# flowhw.net
KiCad netlist of a schematic drawn in Altium Designer
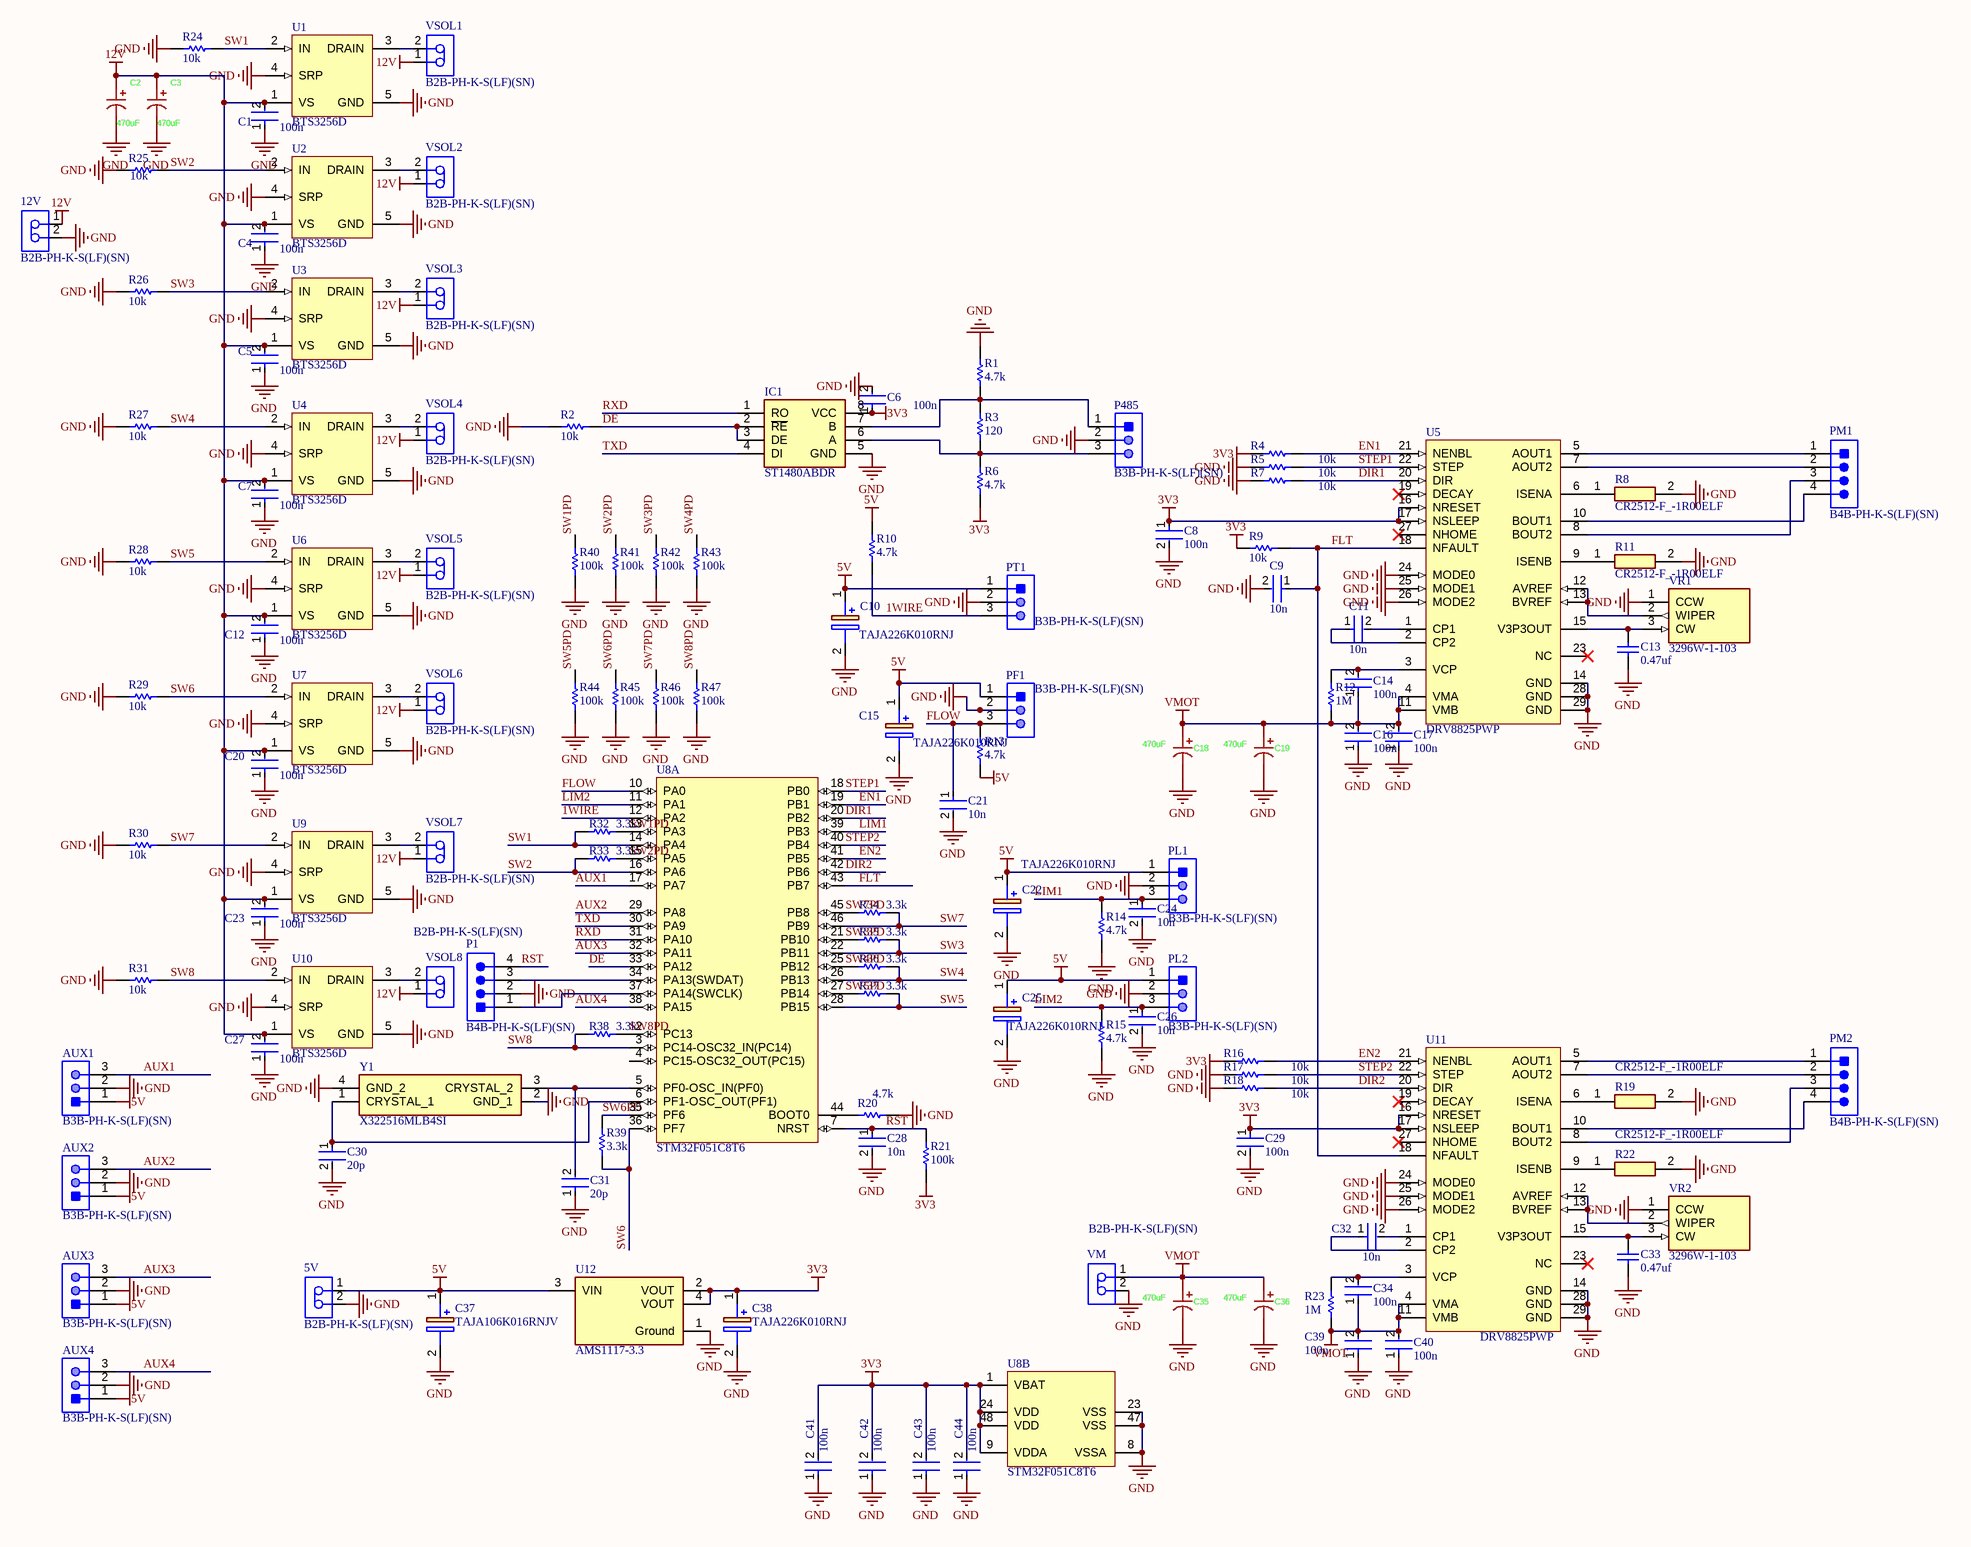
[diagram p0: flowhw.SchDoc]

(export (version "E")
  (design (tool "Eeschema 10.0.6"))
  (components
    (comp (ref "5V")
      (value "B2B-PH-K-S(LF)(SN)")
      (footprint "JST-B2B-PH-K-S_V")
      (fields (field (name "MANUFACTURER") "JST"))
      (libsource (lib "Altium Content Vault") (part "CN-2P-F-QF2"))
    )
    (comp (ref "12V")
      (value "B2B-PH-K-S(LF)(SN)")
      (footprint "JST-B2B-PH-K-S_V")
      (fields (field (name "MANUFACTURER") "JST"))
      (libsource (lib "Altium Content Vault") (part "CN-2P-F-QF2"))
    )
    (comp (ref "AUX1")
      (value "B3B-PH-K-S(LF)(SN)")
      (footprint "JST-B3B-PH-K-S-3_V")
      (fields (field (name "MANUFACTURER") "JST"))
      (libsource (lib "Altium Content Vault") (part "CN-1P-M-R3"))
    )
    (comp (ref "AUX2")
      (value "B3B-PH-K-S(LF)(SN)")
      (footprint "JST-B3B-PH-K-S-3_V")
      (fields (field (name "MANUFACTURER") "JST"))
      (libsource (lib "Altium Content Vault") (part "CN-1P-M-R3"))
    )
    (comp (ref "AUX3")
      (value "B3B-PH-K-S(LF)(SN)")
      (footprint "JST-B3B-PH-K-S-3_V")
      (fields (field (name "MANUFACTURER") "JST"))
      (libsource (lib "Altium Content Vault") (part "CN-1P-M-R3"))
    )
    (comp (ref "AUX4")
      (value "B3B-PH-K-S(LF)(SN)")
      (footprint "JST-B3B-PH-K-S-3_V")
      (fields (field (name "MANUFACTURER") "JST"))
      (libsource (lib "Altium Content Vault") (part "CN-1P-M-R3"))
    )
    (comp (ref "C1")
      (value "100n")
      (footprint "FP-C0402-BB-MFG")
      (description "C0402 8.2 pF C0G 0.5 pF 50 V")
      (fields
        (field (name "OCTOPART") "https://octopart.com/c0402c829d5gacauto-kemet-89441553")
        (field (name "TOLERANCE") "0.5 pF")
      )
      (libsource (lib "Altium Content Vault") (part "b4654b650e69147ec39a6b967a45e02"))
    )
    (comp (ref "C2")
      (value "470uF")
      (footprint "470UF")
      (fields
        (field (name "MANUFACTURER") "AISHI(艾华集团)")
        (field (name "MANUFACTURER PART") "SPZ1VM471G13O00RAXXX")
        (field (name "TOLERANCE") "±20%")
      )
      (libsource (lib "altium-import") (part "root_3_SPZ1VM471G13O00RAXXX_"))
    )
    (comp (ref "C3")
      (value "470uF")
      (footprint "470UF")
      (fields
        (field (name "MANUFACTURER") "AISHI(艾华集团)")
        (field (name "MANUFACTURER PART") "SPZ1VM471G13O00RAXXX")
        (field (name "TOLERANCE") "±20%")
      )
      (libsource (lib "altium-import") (part "root_3_SPZ1VM471G13O00RAXXX_"))
    )
    (comp (ref "C4")
      (value "100n")
      (footprint "FP-C0402-BB-MFG")
      (description "C0402 8.2 pF C0G 0.5 pF 50 V")
      (fields
        (field (name "OCTOPART") "https://octopart.com/c0402c829d5gacauto-kemet-89441553")
        (field (name "TOLERANCE") "0.5 pF")
      )
      (libsource (lib "Altium Content Vault") (part "b4654b650e69147ec39a6b967a45e02"))
    )
    (comp (ref "C5")
      (value "100n")
      (footprint "FP-C0402-BB-MFG")
      (description "C0402 8.2 pF C0G 0.5 pF 50 V")
      (fields
        (field (name "OCTOPART") "https://octopart.com/c0402c829d5gacauto-kemet-89441553")
        (field (name "TOLERANCE") "0.5 pF")
      )
      (libsource (lib "Altium Content Vault") (part "b4654b650e69147ec39a6b967a45e02"))
    )
    (comp (ref "C6")
      (value "100n")
      (footprint "FP-C0402-BB-MFG")
      (description "C0402 8.2 pF C0G 0.5 pF 50 V")
      (fields
        (field (name "OCTOPART") "https://octopart.com/c0402c829d5gacauto-kemet-89441553")
        (field (name "TOLERANCE") "0.5 pF")
      )
      (libsource (lib "Altium Content Vault") (part "b4654b650e69147ec39a6b967a45e02"))
    )
    (comp (ref "C7")
      (value "100n")
      (footprint "FP-C0402-BB-MFG")
      (description "C0402 8.2 pF C0G 0.5 pF 50 V")
      (fields
        (field (name "OCTOPART") "https://octopart.com/c0402c829d5gacauto-kemet-89441553")
        (field (name "TOLERANCE") "0.5 pF")
      )
      (libsource (lib "Altium Content Vault") (part "b4654b650e69147ec39a6b967a45e02"))
    )
    (comp (ref "C8")
      (value "100n")
      (footprint "FP-C0402-BB-MFG")
      (description "C0402 8.2 pF C0G 0.5 pF 50 V")
      (fields
        (field (name "OCTOPART") "https://octopart.com/c0402c829d5gacauto-kemet-89441553")
        (field (name "TOLERANCE") "0.5 pF")
      )
      (libsource (lib "Altium Content Vault") (part "b4654b650e69147ec39a6b967a45e02"))
    )
    (comp (ref "C9")
      (value "10n")
      (footprint "FP-C0402-BB-MFG")
      (description "C0402 8.2 pF C0G 0.5 pF 50 V")
      (fields
        (field (name "OCTOPART") "https://octopart.com/c0402c829d5gacauto-kemet-89441553")
        (field (name "TOLERANCE") "0.5 pF")
      )
      (libsource (lib "Altium Content Vault") (part "b4654b650e69147ec39a6b967a45e02"))
    )
    (comp (ref "C10")
      (value "TAJA226K010RNJ")
      (footprint "SamacSys:CAPPM3216X180N")
      (description "Capacitor Polarised")
      (fields (field (name "MOUSER PART NUMBER") "581-TAJA226K010R"))
      (libsource (lib "*") (part "TAJA226K010RNJ"))
    )
    (comp (ref "C11")
      (value "10n")
      (footprint "FP-C0402-BB-MFG")
      (description "C0402 8.2 pF C0G 0.5 pF 50 V")
      (fields
        (field (name "OCTOPART") "https://octopart.com/c0402c829d5gacauto-kemet-89441553")
        (field (name "TOLERANCE") "0.5 pF")
      )
      (libsource (lib "Altium Content Vault") (part "b4654b650e69147ec39a6b967a45e02"))
    )
    (comp (ref "C12")
      (value "100n")
      (footprint "FP-C0402-BB-MFG")
      (description "C0402 8.2 pF C0G 0.5 pF 50 V")
      (fields
        (field (name "OCTOPART") "https://octopart.com/c0402c829d5gacauto-kemet-89441553")
        (field (name "TOLERANCE") "0.5 pF")
      )
      (libsource (lib "Altium Content Vault") (part "b4654b650e69147ec39a6b967a45e02"))
    )
    (comp (ref "C13")
      (value "0.47uf")
      (footprint "CAPC1608X90X35LL15T15")
      (fields
        (field (name "MANUFACTURER") "AVX Interconnect / Elco")
        (field (name "PART NUMBER") "0603ZC101KAT2A")
      )
      (libsource (lib "Altium Content Vault") (part "CAP"))
    )
    (comp (ref "C14")
      (value "100n")
      (footprint "FP-C0402-BB-MFG")
      (description "C0402 8.2 pF C0G 0.5 pF 50 V")
      (fields
        (field (name "OCTOPART") "https://octopart.com/c0402c829d5gacauto-kemet-89441553")
        (field (name "TOLERANCE") "0.5 pF")
      )
      (libsource (lib "Altium Content Vault") (part "b4654b650e69147ec39a6b967a45e02"))
    )
    (comp (ref "C15")
      (value "TAJA226K010RNJ")
      (footprint "SamacSys:CAPPM3216X180N")
      (description "Capacitor Polarised")
      (fields (field (name "MOUSER PART NUMBER") "581-TAJA226K010R"))
      (libsource (lib "*") (part "TAJA226K010RNJ"))
    )
    (comp (ref "C16")
      (value "100n")
      (footprint "FP-C0402-BB-MFG")
      (description "C0402 8.2 pF C0G 0.5 pF 50 V")
      (fields
        (field (name "OCTOPART") "https://octopart.com/c0402c829d5gacauto-kemet-89441553")
        (field (name "TOLERANCE") "0.5 pF")
      )
      (libsource (lib "Altium Content Vault") (part "b4654b650e69147ec39a6b967a45e02"))
    )
    (comp (ref "C17")
      (value "100n")
      (footprint "FP-C0402-BB-MFG")
      (description "C0402 8.2 pF C0G 0.5 pF 50 V")
      (fields
        (field (name "OCTOPART") "https://octopart.com/c0402c829d5gacauto-kemet-89441553")
        (field (name "TOLERANCE") "0.5 pF")
      )
      (libsource (lib "Altium Content Vault") (part "b4654b650e69147ec39a6b967a45e02"))
    )
    (comp (ref "C18")
      (value "470uF")
      (footprint "470UF")
      (fields
        (field (name "MANUFACTURER") "AISHI(艾华集团)")
        (field (name "MANUFACTURER PART") "SPZ1VM471G13O00RAXXX")
        (field (name "TOLERANCE") "±20%")
      )
      (libsource (lib "altium-import") (part "root_3_SPZ1VM471G13O00RAXXX_"))
    )
    (comp (ref "C19")
      (value "470uF")
      (footprint "470UF")
      (fields
        (field (name "MANUFACTURER") "AISHI(艾华集团)")
        (field (name "MANUFACTURER PART") "SPZ1VM471G13O00RAXXX")
        (field (name "TOLERANCE") "±20%")
      )
      (libsource (lib "altium-import") (part "root_3_SPZ1VM471G13O00RAXXX_"))
    )
    (comp (ref "C20")
      (value "100n")
      (footprint "FP-C0402-BB-MFG")
      (description "C0402 8.2 pF C0G 0.5 pF 50 V")
      (fields
        (field (name "OCTOPART") "https://octopart.com/c0402c829d5gacauto-kemet-89441553")
        (field (name "TOLERANCE") "0.5 pF")
      )
      (libsource (lib "Altium Content Vault") (part "b4654b650e69147ec39a6b967a45e02"))
    )
    (comp (ref "C21")
      (value "10n")
      (footprint "FP-C0402-BB-MFG")
      (description "C0402 8.2 pF C0G 0.5 pF 50 V")
      (fields
        (field (name "OCTOPART") "https://octopart.com/c0402c829d5gacauto-kemet-89441553")
        (field (name "TOLERANCE") "0.5 pF")
      )
      (libsource (lib "Altium Content Vault") (part "b4654b650e69147ec39a6b967a45e02"))
    )
    (comp (ref "C22")
      (value "TAJA226K010RNJ")
      (footprint "SamacSys:CAPPM3216X180N")
      (description "Capacitor Polarised")
      (fields (field (name "MOUSER PART NUMBER") "581-TAJA226K010R"))
      (libsource (lib "*") (part "TAJA226K010RNJ"))
    )
    (comp (ref "C23")
      (value "100n")
      (footprint "FP-C0402-BB-MFG")
      (description "C0402 8.2 pF C0G 0.5 pF 50 V")
      (fields
        (field (name "OCTOPART") "https://octopart.com/c0402c829d5gacauto-kemet-89441553")
        (field (name "TOLERANCE") "0.5 pF")
      )
      (libsource (lib "Altium Content Vault") (part "b4654b650e69147ec39a6b967a45e02"))
    )
    (comp (ref "C24")
      (value "10n")
      (footprint "FP-C0402-BB-MFG")
      (description "C0402 8.2 pF C0G 0.5 pF 50 V")
      (fields
        (field (name "OCTOPART") "https://octopart.com/c0402c829d5gacauto-kemet-89441553")
        (field (name "TOLERANCE") "0.5 pF")
      )
      (libsource (lib "Altium Content Vault") (part "b4654b650e69147ec39a6b967a45e02"))
    )
    (comp (ref "C25")
      (value "TAJA226K010RNJ")
      (footprint "SamacSys:CAPPM3216X180N")
      (description "Capacitor Polarised")
      (fields (field (name "MOUSER PART NUMBER") "581-TAJA226K010R"))
      (libsource (lib "*") (part "TAJA226K010RNJ"))
    )
    (comp (ref "C26")
      (value "10n")
      (footprint "FP-C0402-BB-MFG")
      (description "C0402 8.2 pF C0G 0.5 pF 50 V")
      (fields
        (field (name "OCTOPART") "https://octopart.com/c0402c829d5gacauto-kemet-89441553")
        (field (name "TOLERANCE") "0.5 pF")
      )
      (libsource (lib "Altium Content Vault") (part "b4654b650e69147ec39a6b967a45e02"))
    )
    (comp (ref "C27")
      (value "100n")
      (footprint "FP-C0402-BB-MFG")
      (description "C0402 8.2 pF C0G 0.5 pF 50 V")
      (fields
        (field (name "OCTOPART") "https://octopart.com/c0402c829d5gacauto-kemet-89441553")
        (field (name "TOLERANCE") "0.5 pF")
      )
      (libsource (lib "Altium Content Vault") (part "b4654b650e69147ec39a6b967a45e02"))
    )
    (comp (ref "C28")
      (value "10n")
      (footprint "FP-C0402-BB-MFG")
      (description "C0402 8.2 pF C0G 0.5 pF 50 V")
      (fields
        (field (name "OCTOPART") "https://octopart.com/c0402c829d5gacauto-kemet-89441553")
        (field (name "TOLERANCE") "0.5 pF")
      )
      (libsource (lib "Altium Content Vault") (part "b4654b650e69147ec39a6b967a45e02"))
    )
    (comp (ref "C29")
      (value "100n")
      (footprint "FP-C0402-BB-MFG")
      (description "C0402 8.2 pF C0G 0.5 pF 50 V")
      (fields
        (field (name "OCTOPART") "https://octopart.com/c0402c829d5gacauto-kemet-89441553")
        (field (name "TOLERANCE") "0.5 pF")
      )
      (libsource (lib "Altium Content Vault") (part "b4654b650e69147ec39a6b967a45e02"))
    )
    (comp (ref "C30")
      (value "20p")
      (footprint "FP-C0402-BB-MFG")
      (description "C0402 8.2 pF C0G 0.5 pF 50 V")
      (fields
        (field (name "OCTOPART") "https://octopart.com/c0402c829d5gacauto-kemet-89441553")
        (field (name "TOLERANCE") "0.5 pF")
      )
      (libsource (lib "Altium Content Vault") (part "b4654b650e69147ec39a6b967a45e02"))
    )
    (comp (ref "C31")
      (value "20p")
      (footprint "FP-C0402-BB-MFG")
      (description "C0402 8.2 pF C0G 0.5 pF 50 V")
      (fields
        (field (name "OCTOPART") "https://octopart.com/c0402c829d5gacauto-kemet-89441553")
        (field (name "TOLERANCE") "0.5 pF")
      )
      (libsource (lib "Altium Content Vault") (part "b4654b650e69147ec39a6b967a45e02"))
    )
    (comp (ref "C32")
      (value "10n")
      (footprint "FP-C0402-BB-MFG")
      (description "C0402 8.2 pF C0G 0.5 pF 50 V")
      (fields
        (field (name "OCTOPART") "https://octopart.com/c0402c829d5gacauto-kemet-89441553")
        (field (name "TOLERANCE") "0.5 pF")
      )
      (libsource (lib "Altium Content Vault") (part "b4654b650e69147ec39a6b967a45e02"))
    )
    (comp (ref "C33")
      (value "0.47uf")
      (footprint "CAPC1608X90X35LL15T15")
      (fields
        (field (name "MANUFACTURER") "AVX Interconnect / Elco")
        (field (name "PART NUMBER") "0603ZC101KAT2A")
      )
      (libsource (lib "Altium Content Vault") (part "CAP"))
    )
    (comp (ref "C34")
      (value "100n")
      (footprint "FP-C0402-BB-MFG")
      (description "C0402 8.2 pF C0G 0.5 pF 50 V")
      (fields
        (field (name "OCTOPART") "https://octopart.com/c0402c829d5gacauto-kemet-89441553")
        (field (name "TOLERANCE") "0.5 pF")
      )
      (libsource (lib "Altium Content Vault") (part "b4654b650e69147ec39a6b967a45e02"))
    )
    (comp (ref "C35")
      (value "470uF")
      (footprint "470UF")
      (fields
        (field (name "MANUFACTURER") "AISHI(艾华集团)")
        (field (name "MANUFACTURER PART") "SPZ1VM471G13O00RAXXX")
        (field (name "TOLERANCE") "±20%")
      )
      (libsource (lib "altium-import") (part "root_3_SPZ1VM471G13O00RAXXX_"))
    )
    (comp (ref "C36")
      (value "470uF")
      (footprint "470UF")
      (fields
        (field (name "MANUFACTURER") "AISHI(艾华集团)")
        (field (name "MANUFACTURER PART") "SPZ1VM471G13O00RAXXX")
        (field (name "TOLERANCE") "±20%")
      )
      (libsource (lib "altium-import") (part "root_3_SPZ1VM471G13O00RAXXX_"))
    )
    (comp (ref "C37")
      (value "TAJA106K016RNJV")
      (footprint "SamacSys:CAPPM3216X180N")
      (description "Capacitor Polarised")
      (fields (field (name "MOUSER PART NUMBER") "581-TAJA106K016RNJV"))
      (libsource (lib "*") (part "TAJA106K016RNJV"))
    )
    (comp (ref "C38")
      (value "TAJA226K010RNJ")
      (footprint "SamacSys:CAPPM3216X180N")
      (description "Capacitor Polarised")
      (fields (field (name "MOUSER PART NUMBER") "581-TAJA226K010R"))
      (libsource (lib "*") (part "TAJA226K010RNJ"))
    )
    (comp (ref "C39")
      (value "100n")
      (footprint "FP-C0402-BB-MFG")
      (description "C0402 8.2 pF C0G 0.5 pF 50 V")
      (fields
        (field (name "OCTOPART") "https://octopart.com/c0402c829d5gacauto-kemet-89441553")
        (field (name "TOLERANCE") "0.5 pF")
      )
      (libsource (lib "Altium Content Vault") (part "b4654b650e69147ec39a6b967a45e02"))
    )
    (comp (ref "C40")
      (value "100n")
      (footprint "FP-C0402-BB-MFG")
      (description "C0402 8.2 pF C0G 0.5 pF 50 V")
      (fields
        (field (name "OCTOPART") "https://octopart.com/c0402c829d5gacauto-kemet-89441553")
        (field (name "TOLERANCE") "0.5 pF")
      )
      (libsource (lib "Altium Content Vault") (part "b4654b650e69147ec39a6b967a45e02"))
    )
    (comp (ref "C41")
      (value "100n")
      (footprint "FP-C0402-BB-MFG")
      (description "C0402 8.2 pF C0G 0.5 pF 50 V")
      (fields
        (field (name "OCTOPART") "https://octopart.com/c0402c829d5gacauto-kemet-89441553")
        (field (name "TOLERANCE") "0.5 pF")
      )
      (libsource (lib "Altium Content Vault") (part "b4654b650e69147ec39a6b967a45e02"))
    )
    (comp (ref "C42")
      (value "100n")
      (footprint "FP-C0402-BB-MFG")
      (description "C0402 8.2 pF C0G 0.5 pF 50 V")
      (fields
        (field (name "OCTOPART") "https://octopart.com/c0402c829d5gacauto-kemet-89441553")
        (field (name "TOLERANCE") "0.5 pF")
      )
      (libsource (lib "Altium Content Vault") (part "b4654b650e69147ec39a6b967a45e02"))
    )
    (comp (ref "C43")
      (value "100n")
      (footprint "FP-C0402-BB-MFG")
      (description "C0402 8.2 pF C0G 0.5 pF 50 V")
      (fields
        (field (name "OCTOPART") "https://octopart.com/c0402c829d5gacauto-kemet-89441553")
        (field (name "TOLERANCE") "0.5 pF")
      )
      (libsource (lib "Altium Content Vault") (part "b4654b650e69147ec39a6b967a45e02"))
    )
    (comp (ref "C44")
      (value "100n")
      (footprint "FP-C0402-BB-MFG")
      (description "C0402 8.2 pF C0G 0.5 pF 50 V")
      (fields
        (field (name "OCTOPART") "https://octopart.com/c0402c829d5gacauto-kemet-89441553")
        (field (name "TOLERANCE") "0.5 pF")
      )
      (libsource (lib "Altium Content Vault") (part "b4654b650e69147ec39a6b967a45e02"))
    )
    (comp (ref "IC1")
      (value "ST1480ABDR")
      (footprint "SamacSys:SOIC127P600X175-8N")
      (description "Integrated Circuit")
      (fields (field (name "MOUSER PART NUMBER") "511-ST1480ABDR"))
      (libsource (lib "*") (part "ST1480ABDR"))
    )
    (comp (ref "P1")
      (value "B4B-PH-K-S(LF)(SN)")
      (footprint "JST-B4B-PH-K-S_V")
      (fields (field (name "MANUFACTURER") "JST"))
      (libsource (lib "") (part "CN-1P-M-R4_1"))
    )
    (comp (ref "P485")
      (value "B3B-PH-K-S(LF)(SN)")
      (footprint "JST-B3B-PH-K-S-3_V")
      (fields (field (name "MANUFACTURER") "JST"))
      (libsource (lib "") (part "CN-1P-M-R3_1"))
    )
    (comp (ref "PF1")
      (value "B3B-PH-K-S(LF)(SN)")
      (footprint "JST-B3B-PH-K-S-3_V")
      (fields (field (name "MANUFACTURER") "JST"))
      (libsource (lib "") (part "CN-1P-M-R3_1"))
    )
    (comp (ref "PL1")
      (value "B3B-PH-K-S(LF)(SN)")
      (footprint "JST-B3B-PH-K-S-3_V")
      (fields (field (name "MANUFACTURER") "JST"))
      (libsource (lib "") (part "CN-1P-M-R3_1"))
    )
    (comp (ref "PL2")
      (value "B3B-PH-K-S(LF)(SN)")
      (footprint "JST-B3B-PH-K-S-3_V")
      (fields (field (name "MANUFACTURER") "JST"))
      (libsource (lib "") (part "CN-1P-M-R3_1"))
    )
    (comp (ref "PM1")
      (value "B4B-PH-K-S(LF)(SN)")
      (footprint "JST-B4B-PH-K-S_V")
      (fields (field (name "MANUFACTURER") "JST"))
      (libsource (lib "Altium Content Vault") (part "CN-1P-M-R4"))
    )
    (comp (ref "PM2")
      (value "B4B-PH-K-S(LF)(SN)")
      (footprint "JST-B4B-PH-K-S_V")
      (fields (field (name "MANUFACTURER") "JST"))
      (libsource (lib "Altium Content Vault") (part "CN-1P-M-R4"))
    )
    (comp (ref "PT1")
      (value "B3B-PH-K-S(LF)(SN)")
      (footprint "JST-B3B-PH-K-S-3_V")
      (fields (field (name "MANUFACTURER") "JST"))
      (libsource (lib "") (part "CN-1P-M-R3_1"))
    )
    (comp (ref "R1")
      (value "4.7k")
      (footprint "RESC1005X40X25LL05T10")
      (fields (field (name "PART NUMBER") "RC0402FR-0720R5L") (field (name "MANUFACTURER") "Yageo / Phycomp"))
      (libsource (lib "Altium Content Vault") (part "RES"))
    )
    (comp (ref "R2")
      (value "10k")
      (footprint "RESC1005X40X25LL05T10")
      (fields (field (name "PART NUMBER") "RC0402FR-0720R5L") (field (name "MANUFACTURER") "Yageo / Phycomp"))
      (libsource (lib "Altium Content Vault") (part "RES"))
    )
    (comp (ref "R3")
      (value "120")
      (footprint "RESC1005X40X25LL05T10")
      (fields (field (name "PART NUMBER") "RC0402FR-0720R5L") (field (name "MANUFACTURER") "Yageo / Phycomp"))
      (libsource (lib "Altium Content Vault") (part "RES"))
    )
    (comp (ref "R4")
      (value "10k")
      (footprint "RESC1005X40X25LL05T10")
      (fields (field (name "PART NUMBER") "RC0402FR-0720R5L") (field (name "MANUFACTURER") "Yageo / Phycomp"))
      (libsource (lib "Altium Content Vault") (part "RES"))
    )
    (comp (ref "R5")
      (value "10k")
      (footprint "RESC1005X40X25LL05T10")
      (fields (field (name "PART NUMBER") "RC0402FR-0720R5L") (field (name "MANUFACTURER") "Yageo / Phycomp"))
      (libsource (lib "Altium Content Vault") (part "RES"))
    )
    (comp (ref "R6")
      (value "4.7k")
      (footprint "RESC1005X40X25LL05T10")
      (fields (field (name "PART NUMBER") "RC0402FR-0720R5L") (field (name "MANUFACTURER") "Yageo / Phycomp"))
      (libsource (lib "Altium Content Vault") (part "RES"))
    )
    (comp (ref "R7")
      (value "10k")
      (footprint "RESC1005X40X25LL05T10")
      (fields (field (name "PART NUMBER") "RC0402FR-0720R5L") (field (name "MANUFACTURER") "Yageo / Phycomp"))
      (libsource (lib "Altium Content Vault") (part "RES"))
    )
    (comp (ref "R8")
      (value "CR2512-F_-1R00ELF")
      (footprint "SamacSys:RESC6331X75N")
      (description "Resistor")
      (fields
        (field (name "MANUFACTURER_PART_NUMBER") "CR2512-F/-1R00ELF")
        (field (name "MOUSER PART NUMBER") "652-CR2512-F/1R00ELF")
      )
      (libsource (lib "*") (part "CR2512-F_-1R00ELF"))
    )
    (comp (ref "R9")
      (value "10k")
      (footprint "RESC1005X40X25LL05T10")
      (fields (field (name "PART NUMBER") "RC0402FR-0720R5L") (field (name "MANUFACTURER") "Yageo / Phycomp"))
      (libsource (lib "Altium Content Vault") (part "RES"))
    )
    (comp (ref "R10")
      (value "4.7k")
      (footprint "RESC1005X40X25LL05T10")
      (fields (field (name "PART NUMBER") "RC0402FR-0720R5L") (field (name "MANUFACTURER") "Yageo / Phycomp"))
      (libsource (lib "Altium Content Vault") (part "RES"))
    )
    (comp (ref "R11")
      (value "CR2512-F_-1R00ELF")
      (footprint "SamacSys:RESC6331X75N")
      (description "Resistor")
      (fields
        (field (name "MANUFACTURER_PART_NUMBER") "CR2512-F/-1R00ELF")
        (field (name "MOUSER PART NUMBER") "652-CR2512-F/1R00ELF")
      )
      (libsource (lib "*") (part "CR2512-F_-1R00ELF"))
    )
    (comp (ref "R12")
      (value "1M")
      (footprint "RESC1005X40X25LL05T10")
      (fields (field (name "PART NUMBER") "RC0402FR-0720R5L") (field (name "MANUFACTURER") "Yageo / Phycomp"))
      (libsource (lib "Altium Content Vault") (part "RES"))
    )
    (comp (ref "R13")
      (value "4.7k")
      (footprint "RESC1005X40X25LL05T10")
      (fields (field (name "PART NUMBER") "RC0402FR-0720R5L") (field (name "MANUFACTURER") "Yageo / Phycomp"))
      (libsource (lib "Altium Content Vault") (part "RES"))
    )
    (comp (ref "R14")
      (value "4.7k")
      (footprint "RESC1005X40X25LL05T10")
      (fields (field (name "PART NUMBER") "RC0402FR-0720R5L") (field (name "MANUFACTURER") "Yageo / Phycomp"))
      (libsource (lib "Altium Content Vault") (part "RES"))
    )
    (comp (ref "R15")
      (value "4.7k")
      (footprint "RESC1005X40X25LL05T10")
      (fields (field (name "PART NUMBER") "RC0402FR-0720R5L") (field (name "MANUFACTURER") "Yageo / Phycomp"))
      (libsource (lib "Altium Content Vault") (part "RES"))
    )
    (comp (ref "R16")
      (value "10k")
      (footprint "RESC1005X40X25LL05T10")
      (fields (field (name "PART NUMBER") "RC0402FR-0720R5L") (field (name "MANUFACTURER") "Yageo / Phycomp"))
      (libsource (lib "Altium Content Vault") (part "RES"))
    )
    (comp (ref "R17")
      (value "10k")
      (footprint "RESC1005X40X25LL05T10")
      (fields (field (name "PART NUMBER") "RC0402FR-0720R5L") (field (name "MANUFACTURER") "Yageo / Phycomp"))
      (libsource (lib "Altium Content Vault") (part "RES"))
    )
    (comp (ref "R18")
      (value "10k")
      (footprint "RESC1005X40X25LL05T10")
      (fields (field (name "PART NUMBER") "RC0402FR-0720R5L") (field (name "MANUFACTURER") "Yageo / Phycomp"))
      (libsource (lib "Altium Content Vault") (part "RES"))
    )
    (comp (ref "R19")
      (value "CR2512-F_-1R00ELF")
      (footprint "SamacSys:RESC6331X75N")
      (description "Resistor")
      (fields
        (field (name "MANUFACTURER_PART_NUMBER") "CR2512-F/-1R00ELF")
        (field (name "MOUSER PART NUMBER") "652-CR2512-F/1R00ELF")
      )
      (libsource (lib "*") (part "CR2512-F_-1R00ELF"))
    )
    (comp (ref "R20")
      (value "4.7k")
      (footprint "RESC1005X40X25LL05T10")
      (fields (field (name "PART NUMBER") "RC0402FR-0720R5L") (field (name "MANUFACTURER") "Yageo / Phycomp"))
      (libsource (lib "Altium Content Vault") (part "RES"))
    )
    (comp (ref "R21")
      (value "100k")
      (footprint "RESC1005X40X25LL05T10")
      (fields (field (name "PART NUMBER") "RC0402FR-0720R5L") (field (name "MANUFACTURER") "Yageo / Phycomp"))
      (libsource (lib "Altium Content Vault") (part "RES"))
    )
    (comp (ref "R22")
      (value "CR2512-F_-1R00ELF")
      (footprint "SamacSys:RESC6331X75N")
      (description "Resistor")
      (fields
        (field (name "MANUFACTURER_PART_NUMBER") "CR2512-F/-1R00ELF")
        (field (name "MOUSER PART NUMBER") "652-CR2512-F/1R00ELF")
      )
      (libsource (lib "*") (part "CR2512-F_-1R00ELF"))
    )
    (comp (ref "R23")
      (value "1M")
      (footprint "RESC1005X40X25LL05T10")
      (fields (field (name "PART NUMBER") "RC0402FR-0720R5L") (field (name "MANUFACTURER") "Yageo / Phycomp"))
      (libsource (lib "Altium Content Vault") (part "RES"))
    )
    (comp (ref "R24")
      (value "10k")
      (footprint "RESC1005X40X25LL05T10")
      (fields (field (name "PART NUMBER") "RC0402FR-0720R5L") (field (name "MANUFACTURER") "Yageo / Phycomp"))
      (libsource (lib "Altium Content Vault") (part "RES"))
    )
    (comp (ref "R25")
      (value "10k")
      (footprint "RESC1005X40X25LL05T10")
      (fields (field (name "PART NUMBER") "RC0402FR-0720R5L") (field (name "MANUFACTURER") "Yageo / Phycomp"))
      (libsource (lib "Altium Content Vault") (part "RES"))
    )
    (comp (ref "R26")
      (value "10k")
      (footprint "RESC1005X40X25LL05T10")
      (fields (field (name "PART NUMBER") "RC0402FR-0720R5L") (field (name "MANUFACTURER") "Yageo / Phycomp"))
      (libsource (lib "Altium Content Vault") (part "RES"))
    )
    (comp (ref "R27")
      (value "10k")
      (footprint "RESC1005X40X25LL05T10")
      (fields (field (name "PART NUMBER") "RC0402FR-0720R5L") (field (name "MANUFACTURER") "Yageo / Phycomp"))
      (libsource (lib "Altium Content Vault") (part "RES"))
    )
    (comp (ref "R28")
      (value "10k")
      (footprint "RESC1005X40X25LL05T10")
      (fields (field (name "PART NUMBER") "RC0402FR-0720R5L") (field (name "MANUFACTURER") "Yageo / Phycomp"))
      (libsource (lib "Altium Content Vault") (part "RES"))
    )
    (comp (ref "R29")
      (value "10k")
      (footprint "RESC1005X40X25LL05T10")
      (fields (field (name "PART NUMBER") "RC0402FR-0720R5L") (field (name "MANUFACTURER") "Yageo / Phycomp"))
      (libsource (lib "Altium Content Vault") (part "RES"))
    )
    (comp (ref "R30")
      (value "10k")
      (footprint "RESC1005X40X25LL05T10")
      (fields (field (name "PART NUMBER") "RC0402FR-0720R5L") (field (name "MANUFACTURER") "Yageo / Phycomp"))
      (libsource (lib "Altium Content Vault") (part "RES"))
    )
    (comp (ref "R31")
      (value "10k")
      (footprint "RESC1005X40X25LL05T10")
      (fields (field (name "PART NUMBER") "RC0402FR-0720R5L") (field (name "MANUFACTURER") "Yageo / Phycomp"))
      (libsource (lib "Altium Content Vault") (part "RES"))
    )
    (comp (ref "R32")
      (value "3.3k")
      (footprint "RESC1005X40X25LL05T10")
      (fields (field (name "PART NUMBER") "RC0402FR-0720R5L") (field (name "MANUFACTURER") "Yageo / Phycomp"))
      (libsource (lib "Altium Content Vault") (part "RES"))
    )
    (comp (ref "R33")
      (value "3.3k")
      (footprint "RESC1005X40X25LL05T10")
      (fields (field (name "PART NUMBER") "RC0402FR-0720R5L") (field (name "MANUFACTURER") "Yageo / Phycomp"))
      (libsource (lib "Altium Content Vault") (part "RES"))
    )
    (comp (ref "R34")
      (value "3.3k")
      (footprint "RESC1005X40X25LL05T10")
      (fields (field (name "PART NUMBER") "RC0402FR-0720R5L") (field (name "MANUFACTURER") "Yageo / Phycomp"))
      (libsource (lib "Altium Content Vault") (part "RES"))
    )
    (comp (ref "R35")
      (value "3.3k")
      (footprint "RESC1005X40X25LL05T10")
      (fields (field (name "PART NUMBER") "RC0402FR-0720R5L") (field (name "MANUFACTURER") "Yageo / Phycomp"))
      (libsource (lib "Altium Content Vault") (part "RES"))
    )
    (comp (ref "R36")
      (value "3.3k")
      (footprint "RESC1005X40X25LL05T10")
      (fields (field (name "PART NUMBER") "RC0402FR-0720R5L") (field (name "MANUFACTURER") "Yageo / Phycomp"))
      (libsource (lib "Altium Content Vault") (part "RES"))
    )
    (comp (ref "R37")
      (value "3.3k")
      (footprint "RESC1005X40X25LL05T10")
      (fields (field (name "PART NUMBER") "RC0402FR-0720R5L") (field (name "MANUFACTURER") "Yageo / Phycomp"))
      (libsource (lib "Altium Content Vault") (part "RES"))
    )
    (comp (ref "R38")
      (value "3.3k")
      (footprint "RESC1005X40X25LL05T10")
      (fields (field (name "PART NUMBER") "RC0402FR-0720R5L") (field (name "MANUFACTURER") "Yageo / Phycomp"))
      (libsource (lib "Altium Content Vault") (part "RES"))
    )
    (comp (ref "R39")
      (value "3.3k")
      (footprint "RESC1005X40X25LL05T10")
      (fields (field (name "PART NUMBER") "RC0402FR-0720R5L") (field (name "MANUFACTURER") "Yageo / Phycomp"))
      (libsource (lib "Altium Content Vault") (part "RES"))
    )
    (comp (ref "R40")
      (value "100k")
      (footprint "RESC1005X40X25LL05T10")
      (fields (field (name "PART NUMBER") "RC0402FR-0720R5L") (field (name "MANUFACTURER") "Yageo / Phycomp"))
      (libsource (lib "Altium Content Vault") (part "RES"))
    )
    (comp (ref "R41")
      (value "100k")
      (footprint "RESC1005X40X25LL05T10")
      (fields (field (name "PART NUMBER") "RC0402FR-0720R5L") (field (name "MANUFACTURER") "Yageo / Phycomp"))
      (libsource (lib "Altium Content Vault") (part "RES"))
    )
    (comp (ref "R42")
      (value "100k")
      (footprint "RESC1005X40X25LL05T10")
      (fields (field (name "PART NUMBER") "RC0402FR-0720R5L") (field (name "MANUFACTURER") "Yageo / Phycomp"))
      (libsource (lib "Altium Content Vault") (part "RES"))
    )
    (comp (ref "R43")
      (value "100k")
      (footprint "RESC1005X40X25LL05T10")
      (fields (field (name "PART NUMBER") "RC0402FR-0720R5L") (field (name "MANUFACTURER") "Yageo / Phycomp"))
      (libsource (lib "Altium Content Vault") (part "RES"))
    )
    (comp (ref "R44")
      (value "100k")
      (footprint "RESC1005X40X25LL05T10")
      (fields (field (name "PART NUMBER") "RC0402FR-0720R5L") (field (name "MANUFACTURER") "Yageo / Phycomp"))
      (libsource (lib "Altium Content Vault") (part "RES"))
    )
    (comp (ref "R45")
      (value "100k")
      (footprint "RESC1005X40X25LL05T10")
      (fields (field (name "PART NUMBER") "RC0402FR-0720R5L") (field (name "MANUFACTURER") "Yageo / Phycomp"))
      (libsource (lib "Altium Content Vault") (part "RES"))
    )
    (comp (ref "R46")
      (value "100k")
      (footprint "RESC1005X40X25LL05T10")
      (fields (field (name "PART NUMBER") "RC0402FR-0720R5L") (field (name "MANUFACTURER") "Yageo / Phycomp"))
      (libsource (lib "Altium Content Vault") (part "RES"))
    )
    (comp (ref "R47")
      (value "100k")
      (footprint "RESC1005X40X25LL05T10")
      (fields (field (name "PART NUMBER") "RC0402FR-0720R5L") (field (name "MANUFACTURER") "Yageo / Phycomp"))
      (libsource (lib "Altium Content Vault") (part "RES"))
    )
    (comp (ref "U1")
      (value "BTS3256D")
      (footprint "INF-PG-TO252-5-1_M")
      (fields (field (name "MANUFACTURER") "Infineon"))
      (libsource (lib "Altium Content Vault") (part "INF-BTS3256D-PG-TO252-5-11-4"))
    )
    (comp (ref "U2")
      (value "BTS3256D")
      (footprint "INF-PG-TO252-5-1_M")
      (fields (field (name "MANUFACTURER") "Infineon"))
      (libsource (lib "Altium Content Vault") (part "INF-BTS3256D-PG-TO252-5-11-4"))
    )
    (comp (ref "U3")
      (value "BTS3256D")
      (footprint "INF-PG-TO252-5-1_M")
      (fields (field (name "MANUFACTURER") "Infineon"))
      (libsource (lib "Altium Content Vault") (part "INF-BTS3256D-PG-TO252-5-11-4"))
    )
    (comp (ref "U4")
      (value "BTS3256D")
      (footprint "INF-PG-TO252-5-1_M")
      (fields (field (name "MANUFACTURER") "Infineon"))
      (libsource (lib "Altium Content Vault") (part "INF-BTS3256D-PG-TO252-5-11-4"))
    )
    (comp (ref "U5")
      (value "DRV8825PWP")
      (footprint "PWP0028C_L")
      (fields (field (name "TOLERANCE") "20%"))
      (libsource (lib "Altium Content Vault") (part "TI-DRV882XPWP28-XXXXXXXXXTP"))
    )
    (comp (ref "U6")
      (value "BTS3256D")
      (footprint "INF-PG-TO252-5-1_M")
      (fields (field (name "MANUFACTURER") "Infineon"))
      (libsource (lib "Altium Content Vault") (part "INF-BTS3256D-PG-TO252-5-11-4"))
    )
    (comp (ref "U7")
      (value "BTS3256D")
      (footprint "INF-PG-TO252-5-1_M")
      (fields (field (name "MANUFACTURER") "Infineon"))
      (libsource (lib "Altium Content Vault") (part "INF-BTS3256D-PG-TO252-5-11-4"))
    )
    (comp (ref "U8")
      (value "STM32F051C8T6")
      (footprint "STM-LQFP48_N")
      (libsource (lib "Altium Content Vault") (part "MC-ARM-STM32F051-SQ48"))
    )
    (comp (ref "U9")
      (value "BTS3256D")
      (footprint "INF-PG-TO252-5-1_M")
      (fields (field (name "MANUFACTURER") "Infineon"))
      (libsource (lib "Altium Content Vault") (part "INF-BTS3256D-PG-TO252-5-11-4"))
    )
    (comp (ref "U10")
      (value "BTS3256D")
      (footprint "INF-PG-TO252-5-1_M")
      (fields (field (name "MANUFACTURER") "Infineon"))
      (libsource (lib "Altium Content Vault") (part "INF-BTS3256D-PG-TO252-5-11-4"))
    )
    (comp (ref "U11")
      (value "DRV8825PWP")
      (footprint "PWP0028C_L")
      (fields (field (name "TOLERANCE") "20%"))
      (libsource (lib "Altium Content Vault") (part "TI-DRV882XPWP28-XXXXXXXXXTP"))
    )
    (comp (ref "U12")
      (value "AMS1117-3.3")
      (footprint "FP-AMS1117-IPC_C")
      (description "LDO Voltage Regulators 1A, 3.3V")
      (fields
        (field (name "OCTOPART") "https://octopart.com/ams1117-3.3-advanced+monolithic+systems-25899300")
        (field (name "MANUFACTURER") "Advanced Monolithic Systems")
      )
      (libsource (lib "Altium Content Vault") (part "8bdbb5f8e77002000e30dd2845d0354"))
    )
    (comp (ref "VM")
      (value "B2B-PH-K-S(LF)(SN)")
      (footprint "JST-B2B-PH-K-S_V")
      (fields (field (name "MANUFACTURER") "JST"))
      (libsource (lib "Altium Content Vault") (part "CN-2P-F-QF2"))
    )
    (comp (ref "VR1")
      (value "3296W-1-103")
      (footprint "SamacSys:3296W1103")
      (description "Variable Resistor")
      (libsource (lib "*") (part "3296W-1-103"))
    )
    (comp (ref "VR2")
      (value "3296W-1-103")
      (footprint "SamacSys:3296W1103")
      (description "Variable Resistor")
      (libsource (lib "*") (part "3296W-1-103"))
    )
    (comp (ref "VSOL1")
      (value "B2B-PH-K-S(LF)(SN)")
      (footprint "JST-B2B-PH-K-S_V")
      (fields (field (name "MANUFACTURER") "JST"))
      (libsource (lib "Altium Content Vault") (part "CN-2P-F-QF2"))
    )
    (comp (ref "VSOL2")
      (value "B2B-PH-K-S(LF)(SN)")
      (footprint "JST-B2B-PH-K-S_V")
      (fields (field (name "MANUFACTURER") "JST"))
      (libsource (lib "Altium Content Vault") (part "CN-2P-F-QF2"))
    )
    (comp (ref "VSOL3")
      (value "B2B-PH-K-S(LF)(SN)")
      (footprint "JST-B2B-PH-K-S_V")
      (fields (field (name "MANUFACTURER") "JST"))
      (libsource (lib "Altium Content Vault") (part "CN-2P-F-QF2"))
    )
    (comp (ref "VSOL4")
      (value "B2B-PH-K-S(LF)(SN)")
      (footprint "JST-B2B-PH-K-S_V")
      (fields (field (name "MANUFACTURER") "JST"))
      (libsource (lib "Altium Content Vault") (part "CN-2P-F-QF2"))
    )
    (comp (ref "VSOL5")
      (value "B2B-PH-K-S(LF)(SN)")
      (footprint "JST-B2B-PH-K-S_V")
      (fields (field (name "MANUFACTURER") "JST"))
      (libsource (lib "Altium Content Vault") (part "CN-2P-F-QF2"))
    )
    (comp (ref "VSOL6")
      (value "B2B-PH-K-S(LF)(SN)")
      (footprint "JST-B2B-PH-K-S_V")
      (fields (field (name "MANUFACTURER") "JST"))
      (libsource (lib "Altium Content Vault") (part "CN-2P-F-QF2"))
    )
    (comp (ref "VSOL7")
      (value "B2B-PH-K-S(LF)(SN)")
      (footprint "JST-B2B-PH-K-S_V")
      (fields (field (name "MANUFACTURER") "JST"))
      (libsource (lib "Altium Content Vault") (part "CN-2P-F-QF2"))
    )
    (comp (ref "VSOL8")
      (value "B2B-PH-K-S(LF)(SN)")
      (footprint "JST-B2B-PH-K-S_V")
      (fields (field (name "MANUFACTURER") "JST"))
      (libsource (lib "Altium Content Vault") (part "CN-2P-F-QF2"))
    )
    (comp (ref "Y1")
      (value "X322516MLB4SI")
      (footprint "SamacSys:X322516MLB4SI")
      (description "Crystal or Oscillator")
      (libsource (lib "*") (part "X322516MLB4SI"))
    )
  )
  (nets
    (net (code "1") (name "/1WIRE") (class "Default")
      (node (ref "PT1") (pin "3") (pinfunction "3_3") (pintype "passive"))
      (node (ref "R10") (pin "2") (pinfunction "2_2") (pintype "passive"))
      (node (ref "U8") (pin "12") (pinfunction "PA2_12") (pintype "bidirectional"))
    )
    (net (code "2") (name "/AUX1") (class "Default")
      (node (ref "AUX1") (pin "3") (pinfunction "3_3") (pintype "passive"))
      (node (ref "U8") (pin "17") (pinfunction "PA7_17") (pintype "bidirectional"))
    )
    (net (code "3") (name "/AUX2") (class "Default")
      (node (ref "AUX2") (pin "3") (pinfunction "3_3") (pintype "passive"))
      (node (ref "U8") (pin "29") (pinfunction "PA8_29") (pintype "bidirectional"))
    )
    (net (code "4") (name "/AUX3") (class "Default")
      (node (ref "AUX3") (pin "3") (pinfunction "3_3") (pintype "passive"))
      (node (ref "U8") (pin "32") (pinfunction "PA11_32") (pintype "bidirectional"))
    )
    (net (code "5") (name "/AUX4") (class "Default")
      (node (ref "AUX4") (pin "3") (pinfunction "3_3") (pintype "passive"))
      (node (ref "U8") (pin "38") (pinfunction "PA15_38") (pintype "bidirectional"))
    )
    (net (code "6") (name "/DE") (class "Default")
      (node (ref "IC1") (pin "2") (pinfunction "~{RE}_2") (pintype "passive"))
      (node (ref "IC1") (pin "3") (pinfunction "DE_3") (pintype "passive"))
      (node (ref "R2") (pin "1") (pinfunction "1_1") (pintype "passive"))
      (node (ref "U8") (pin "33") (pinfunction "PA12_33") (pintype "bidirectional"))
    )
    (net (code "7") (name "/DIR1") (class "Default")
      (node (ref "R7") (pin "2") (pinfunction "2_2") (pintype "passive"))
      (node (ref "U5") (pin "20") (pinfunction "DIR_20") (pintype "input"))
      (node (ref "U8") (pin "20") (pinfunction "PB2_20") (pintype "bidirectional"))
    )
    (net (code "8") (name "/DIR2") (class "Default")
      (node (ref "R18") (pin "2") (pinfunction "2_2") (pintype "passive"))
      (node (ref "U11") (pin "20") (pinfunction "DIR_20") (pintype "input"))
      (node (ref "U8") (pin "42") (pinfunction "PB6_42") (pintype "bidirectional"))
    )
    (net (code "9") (name "/EN1") (class "Default")
      (node (ref "R4") (pin "2") (pinfunction "2_2") (pintype "passive"))
      (node (ref "U5") (pin "21") (pinfunction "NENBL_21") (pintype "input"))
      (node (ref "U8") (pin "19") (pinfunction "PB1_19") (pintype "bidirectional"))
    )
    (net (code "10") (name "/EN2") (class "Default")
      (node (ref "R16") (pin "2") (pinfunction "2_2") (pintype "passive"))
      (node (ref "U11") (pin "21") (pinfunction "NENBL_21") (pintype "input"))
      (node (ref "U8") (pin "41") (pinfunction "PB5_41") (pintype "bidirectional"))
    )
    (net (code "11") (name "/FLOW") (class "Default")
      (node (ref "C21") (pin "1") (pinfunction "1_1") (pintype "passive"))
      (node (ref "PF1") (pin "3") (pinfunction "3_3") (pintype "passive"))
      (node (ref "R13") (pin "1") (pinfunction "1_1") (pintype "passive"))
      (node (ref "U8") (pin "10") (pinfunction "PA0_10") (pintype "bidirectional"))
    )
    (net (code "12") (name "/FLT") (class "Default")
      (node (ref "C9") (pin "1") (pinfunction "1_1") (pintype "passive"))
      (node (ref "R9") (pin "2") (pinfunction "2_2") (pintype "passive"))
      (node (ref "U11") (pin "18") (pinfunction "NFAULT_18") (pintype "open_collector"))
      (node (ref "U5") (pin "18") (pinfunction "NFAULT_18") (pintype "open_collector"))
      (node (ref "U8") (pin "43") (pinfunction "PB7_43") (pintype "bidirectional"))
    )
    (net (code "13") (name "/LIM1") (class "Default")
      (node (ref "C24") (pin "1") (pinfunction "1_1") (pintype "passive"))
      (node (ref "PL1") (pin "3") (pinfunction "3_3") (pintype "passive"))
      (node (ref "R14") (pin "1") (pinfunction "1_1") (pintype "passive"))
      (node (ref "U8") (pin "39") (pinfunction "PB3_39") (pintype "bidirectional"))
    )
    (net (code "14") (name "/LIM2") (class "Default")
      (node (ref "C26") (pin "1") (pinfunction "1_1") (pintype "passive"))
      (node (ref "PL2") (pin "3") (pinfunction "3_3") (pintype "passive"))
      (node (ref "R15") (pin "1") (pinfunction "1_1") (pintype "passive"))
      (node (ref "U8") (pin "11") (pinfunction "PA1_11") (pintype "bidirectional"))
    )
    (net (code "15") (name "/RST") (class "Default")
      (node (ref "C28") (pin "1") (pinfunction "1_1") (pintype "passive"))
      (node (ref "P1") (pin "4") (pinfunction "4_4") (pintype "passive"))
      (node (ref "R21") (pin "1") (pinfunction "1_1") (pintype "passive"))
      (node (ref "U8") (pin "7") (pinfunction "NRST_7") (pintype "bidirectional"))
    )
    (net (code "16") (name "/RXD") (class "Default")
      (node (ref "IC1") (pin "1") (pinfunction "RO_1") (pintype "passive"))
      (node (ref "U8") (pin "31") (pinfunction "PA10_31") (pintype "bidirectional"))
    )
    (net (code "17") (name "/STEP1") (class "Default")
      (node (ref "R5") (pin "2") (pinfunction "2_2") (pintype "passive"))
      (node (ref "U5") (pin "22") (pinfunction "STEP_22") (pintype "input"))
      (node (ref "U8") (pin "18") (pinfunction "PB0_18") (pintype "bidirectional"))
    )
    (net (code "18") (name "/STEP2") (class "Default")
      (node (ref "R17") (pin "2") (pinfunction "2_2") (pintype "passive"))
      (node (ref "U11") (pin "22") (pinfunction "STEP_22") (pintype "input"))
      (node (ref "U8") (pin "40") (pinfunction "PB4_40") (pintype "bidirectional"))
    )
    (net (code "19") (name "/SW1") (class "Default")
      (node (ref "R24") (pin "1") (pinfunction "1_1") (pintype "passive"))
      (node (ref "R32") (pin "2") (pinfunction "2_2") (pintype "passive"))
      (node (ref "U1") (pin "2") (pinfunction "IN_2") (pintype "input"))
      (node (ref "U8") (pin "14") (pinfunction "PA4_14") (pintype "bidirectional"))
    )
    (net (code "20") (name "/SW1PD") (class "Default")
      (node (ref "R32") (pin "1") (pinfunction "1_1") (pintype "passive"))
      (node (ref "R40") (pin "1") (pinfunction "1_1") (pintype "passive"))
      (node (ref "U8") (pin "13") (pinfunction "PA3_13") (pintype "bidirectional"))
    )
    (net (code "21") (name "/SW2") (class "Default")
      (node (ref "R25") (pin "1") (pinfunction "1_1") (pintype "passive"))
      (node (ref "R33") (pin "2") (pinfunction "2_2") (pintype "passive"))
      (node (ref "U2") (pin "2") (pinfunction "IN_2") (pintype "input"))
      (node (ref "U8") (pin "16") (pinfunction "PA6_16") (pintype "bidirectional"))
    )
    (net (code "22") (name "/SW2PD") (class "Default")
      (node (ref "R33") (pin "1") (pinfunction "1_1") (pintype "passive"))
      (node (ref "R41") (pin "1") (pinfunction "1_1") (pintype "passive"))
      (node (ref "U8") (pin "15") (pinfunction "PA5_15") (pintype "bidirectional"))
    )
    (net (code "23") (name "/SW3") (class "Default")
      (node (ref "R26") (pin "1") (pinfunction "1_1") (pintype "passive"))
      (node (ref "R35") (pin "1") (pinfunction "1_1") (pintype "passive"))
      (node (ref "U3") (pin "2") (pinfunction "IN_2") (pintype "input"))
      (node (ref "U8") (pin "22") (pinfunction "PB11_22") (pintype "bidirectional"))
    )
    (net (code "24") (name "/SW3PD") (class "Default")
      (node (ref "R35") (pin "2") (pinfunction "2_2") (pintype "passive"))
      (node (ref "R42") (pin "1") (pinfunction "1_1") (pintype "passive"))
      (node (ref "U8") (pin "21") (pinfunction "PB10_21") (pintype "bidirectional"))
    )
    (net (code "25") (name "/SW4") (class "Default")
      (node (ref "R27") (pin "1") (pinfunction "1_1") (pintype "passive"))
      (node (ref "R36") (pin "1") (pinfunction "1_1") (pintype "passive"))
      (node (ref "U4") (pin "2") (pinfunction "IN_2") (pintype "input"))
      (node (ref "U8") (pin "26") (pinfunction "PB13_26") (pintype "bidirectional"))
    )
    (net (code "26") (name "/SW4PD") (class "Default")
      (node (ref "R36") (pin "2") (pinfunction "2_2") (pintype "passive"))
      (node (ref "R43") (pin "1") (pinfunction "1_1") (pintype "passive"))
      (node (ref "U8") (pin "25") (pinfunction "PB12_25") (pintype "bidirectional"))
    )
    (net (code "27") (name "/SW5") (class "Default")
      (node (ref "R28") (pin "1") (pinfunction "1_1") (pintype "passive"))
      (node (ref "R37") (pin "1") (pinfunction "1_1") (pintype "passive"))
      (node (ref "U6") (pin "2") (pinfunction "IN_2") (pintype "input"))
      (node (ref "U8") (pin "28") (pinfunction "PB15_28") (pintype "bidirectional"))
    )
    (net (code "28") (name "/SW5PD") (class "Default")
      (node (ref "R37") (pin "2") (pinfunction "2_2") (pintype "passive"))
      (node (ref "R44") (pin "1") (pinfunction "1_1") (pintype "passive"))
      (node (ref "U8") (pin "27") (pinfunction "PB14_27") (pintype "bidirectional"))
    )
    (net (code "29") (name "/SW6") (class "Default")
      (node (ref "R29") (pin "1") (pinfunction "1_1") (pintype "passive"))
      (node (ref "R39") (pin "2") (pinfunction "2_2") (pintype "passive"))
      (node (ref "U7") (pin "2") (pinfunction "IN_2") (pintype "input"))
      (node (ref "U8") (pin "36") (pinfunction "PF7_36") (pintype "bidirectional"))
    )
    (net (code "30") (name "/SW6PD") (class "Default")
      (node (ref "R39") (pin "1") (pinfunction "1_1") (pintype "passive"))
      (node (ref "R45") (pin "1") (pinfunction "1_1") (pintype "passive"))
      (node (ref "U8") (pin "35") (pinfunction "PF6_35") (pintype "bidirectional"))
    )
    (net (code "31") (name "/SW7") (class "Default")
      (node (ref "R30") (pin "1") (pinfunction "1_1") (pintype "passive"))
      (node (ref "R34") (pin "1") (pinfunction "1_1") (pintype "passive"))
      (node (ref "U8") (pin "46") (pinfunction "PB9_46") (pintype "bidirectional"))
      (node (ref "U9") (pin "2") (pinfunction "IN_2") (pintype "input"))
    )
    (net (code "32") (name "/SW7PD") (class "Default")
      (node (ref "R34") (pin "2") (pinfunction "2_2") (pintype "passive"))
      (node (ref "R46") (pin "1") (pinfunction "1_1") (pintype "passive"))
      (node (ref "U8") (pin "45") (pinfunction "PB8_45") (pintype "bidirectional"))
    )
    (net (code "33") (name "/SW8") (class "Default")
      (node (ref "R31") (pin "1") (pinfunction "1_1") (pintype "passive"))
      (node (ref "R38") (pin "2") (pinfunction "2_2") (pintype "passive"))
      (node (ref "U10") (pin "2") (pinfunction "IN_2") (pintype "input"))
      (node (ref "U8") (pin "3") (pinfunction "PC14-OSC32_IN(PC14)_3") (pintype "bidirectional"))
    )
    (net (code "34") (name "/SW8PD") (class "Default")
      (node (ref "R38") (pin "1") (pinfunction "1_1") (pintype "passive"))
      (node (ref "R47") (pin "1") (pinfunction "1_1") (pintype "passive"))
      (node (ref "U8") (pin "2") (pinfunction "PC13_2") (pintype "bidirectional"))
    )
    (net (code "35") (name "/TXD") (class "Default")
      (node (ref "IC1") (pin "4") (pinfunction "DI_4") (pintype "passive"))
      (node (ref "U8") (pin "30") (pinfunction "PA9_30") (pintype "bidirectional"))
    )
    (net (code "36") (name "3V3") (class "Default")
      (node (ref "C29") (pin "1") (pinfunction "1_1") (pintype "passive"))
      (node (ref "C38") (pin "1") (pinfunction "+_1") (pintype "passive"))
      (node (ref "C41") (pin "2") (pinfunction "2_2") (pintype "passive"))
      (node (ref "C42") (pin "2") (pinfunction "2_2") (pintype "passive"))
      (node (ref "C43") (pin "2") (pinfunction "2_2") (pintype "passive"))
      (node (ref "C44") (pin "2") (pinfunction "2_2") (pintype "passive"))
      (node (ref "C6") (pin "1") (pinfunction "1_1") (pintype "passive"))
      (node (ref "C8") (pin "1") (pinfunction "1_1") (pintype "passive"))
      (node (ref "IC1") (pin "8") (pinfunction "VCC_8") (pintype "passive"))
      (node (ref "R16") (pin "1") (pinfunction "1_1") (pintype "passive"))
      (node (ref "R21") (pin "2") (pinfunction "2_2") (pintype "passive"))
      (node (ref "R4") (pin "1") (pinfunction "1_1") (pintype "passive"))
      (node (ref "R6") (pin "2") (pinfunction "2_2") (pintype "passive"))
      (node (ref "R9") (pin "1") (pinfunction "1_1") (pintype "passive"))
      (node (ref "U11") (pin "16") (pinfunction "NRESET_16") (pintype "input"))
      (node (ref "U11") (pin "17") (pinfunction "NSLEEP_17") (pintype "input"))
      (node (ref "U12") (pin "2") (pinfunction "VOUT_2") (pintype "power_in"))
      (node (ref "U12") (pin "4") (pinfunction "VOUT_4") (pintype "power_in"))
      (node (ref "U5") (pin "16") (pinfunction "NRESET_16") (pintype "input"))
      (node (ref "U5") (pin "17") (pinfunction "NSLEEP_17") (pintype "input"))
      (node (ref "U8") (pin "1") (pinfunction "VBAT_1") (pintype "power_in"))
      (node (ref "U8") (pin "24") (pinfunction "VDD_24") (pintype "power_in"))
      (node (ref "U8") (pin "48") (pinfunction "VDD_48") (pintype "power_in"))
      (node (ref "U8") (pin "9") (pinfunction "VDDA_9") (pintype "power_in"))
    )
    (net (code "37") (name "5V") (class "Default")
      (node (ref "5V") (pin "1") (pinfunction "1_1") (pintype "passive"))
      (node (ref "AUX1") (pin "1") (pinfunction "1_1") (pintype "passive"))
      (node (ref "AUX2") (pin "1") (pinfunction "1_1") (pintype "passive"))
      (node (ref "AUX3") (pin "1") (pinfunction "1_1") (pintype "passive"))
      (node (ref "AUX4") (pin "1") (pinfunction "1_1") (pintype "passive"))
      (node (ref "C10") (pin "1") (pinfunction "+_1") (pintype "passive"))
      (node (ref "C15") (pin "1") (pinfunction "+_1") (pintype "passive"))
      (node (ref "C22") (pin "1") (pinfunction "+_1") (pintype "passive"))
      (node (ref "C25") (pin "1") (pinfunction "+_1") (pintype "passive"))
      (node (ref "C37") (pin "1") (pinfunction "+_1") (pintype "passive"))
      (node (ref "PF1") (pin "1") (pinfunction "1_1") (pintype "passive"))
      (node (ref "PL1") (pin "1") (pinfunction "1_1") (pintype "passive"))
      (node (ref "PL2") (pin "1") (pinfunction "1_1") (pintype "passive"))
      (node (ref "PT1") (pin "1") (pinfunction "1_1") (pintype "passive"))
      (node (ref "R10") (pin "1") (pinfunction "1_1") (pintype "passive"))
      (node (ref "R13") (pin "2") (pinfunction "2_2") (pintype "passive"))
      (node (ref "U12") (pin "3") (pinfunction "VIN_3") (pintype "power_in"))
    )
    (net (code "38") (name "12V") (class "Default")
      (node (ref "12V") (pin "1") (pinfunction "1_1") (pintype "passive"))
      (node (ref "C1") (pin "2") (pinfunction "2_2") (pintype "passive"))
      (node (ref "C12") (pin "2") (pinfunction "2_2") (pintype "passive"))
      (node (ref "C2") (pin "1") (pinfunction "1_1") (pintype "passive"))
      (node (ref "C20") (pin "2") (pinfunction "2_2") (pintype "passive"))
      (node (ref "C23") (pin "2") (pinfunction "2_2") (pintype "passive"))
      (node (ref "C27") (pin "2") (pinfunction "2_2") (pintype "passive"))
      (node (ref "C3") (pin "1") (pinfunction "1_1") (pintype "passive"))
      (node (ref "C4") (pin "2") (pinfunction "2_2") (pintype "passive"))
      (node (ref "C5") (pin "2") (pinfunction "2_2") (pintype "passive"))
      (node (ref "C7") (pin "2") (pinfunction "2_2") (pintype "passive"))
      (node (ref "U1") (pin "1") (pinfunction "VS_1") (pintype "power_in"))
      (node (ref "U10") (pin "1") (pinfunction "VS_1") (pintype "power_in"))
      (node (ref "U2") (pin "1") (pinfunction "VS_1") (pintype "power_in"))
      (node (ref "U3") (pin "1") (pinfunction "VS_1") (pintype "power_in"))
      (node (ref "U4") (pin "1") (pinfunction "VS_1") (pintype "power_in"))
      (node (ref "U6") (pin "1") (pinfunction "VS_1") (pintype "power_in"))
      (node (ref "U7") (pin "1") (pinfunction "VS_1") (pintype "power_in"))
      (node (ref "U9") (pin "1") (pinfunction "VS_1") (pintype "power_in"))
      (node (ref "VSOL1") (pin "1") (pinfunction "1_1") (pintype "passive"))
      (node (ref "VSOL2") (pin "1") (pinfunction "1_1") (pintype "passive"))
      (node (ref "VSOL3") (pin "1") (pinfunction "1_1") (pintype "passive"))
      (node (ref "VSOL4") (pin "1") (pinfunction "1_1") (pintype "passive"))
      (node (ref "VSOL5") (pin "1") (pinfunction "1_1") (pintype "passive"))
      (node (ref "VSOL6") (pin "1") (pinfunction "1_1") (pintype "passive"))
      (node (ref "VSOL7") (pin "1") (pinfunction "1_1") (pintype "passive"))
      (node (ref "VSOL8") (pin "1") (pinfunction "1_1") (pintype "passive"))
    )
    (net (code "39") (name "GND") (class "Default")
      (node (ref "12V") (pin "2") (pinfunction "2_2") (pintype "passive"))
      (node (ref "5V") (pin "2") (pinfunction "2_2") (pintype "passive"))
      (node (ref "AUX1") (pin "2") (pinfunction "2_2") (pintype "passive"))
      (node (ref "AUX2") (pin "2") (pinfunction "2_2") (pintype "passive"))
      (node (ref "AUX3") (pin "2") (pinfunction "2_2") (pintype "passive"))
      (node (ref "AUX4") (pin "2") (pinfunction "2_2") (pintype "passive"))
      (node (ref "C1") (pin "1") (pinfunction "1_1") (pintype "passive"))
      (node (ref "C10") (pin "2") (pinfunction "-_2") (pintype "passive"))
      (node (ref "C12") (pin "1") (pinfunction "1_1") (pintype "passive"))
      (node (ref "C13") (pin "1") (pinfunction "1_1") (pintype "passive"))
      (node (ref "C15") (pin "2") (pinfunction "-_2") (pintype "passive"))
      (node (ref "C16") (pin "1") (pinfunction "1_1") (pintype "passive"))
      (node (ref "C17") (pin "1") (pinfunction "1_1") (pintype "passive"))
      (node (ref "C18") (pin "2") (pinfunction "2_2") (pintype "passive"))
      (node (ref "C19") (pin "2") (pinfunction "2_2") (pintype "passive"))
      (node (ref "C2") (pin "2") (pinfunction "2_2") (pintype "passive"))
      (node (ref "C20") (pin "1") (pinfunction "1_1") (pintype "passive"))
      (node (ref "C21") (pin "2") (pinfunction "2_2") (pintype "passive"))
      (node (ref "C22") (pin "2") (pinfunction "-_2") (pintype "passive"))
      (node (ref "C23") (pin "1") (pinfunction "1_1") (pintype "passive"))
      (node (ref "C24") (pin "2") (pinfunction "2_2") (pintype "passive"))
      (node (ref "C25") (pin "2") (pinfunction "-_2") (pintype "passive"))
      (node (ref "C26") (pin "2") (pinfunction "2_2") (pintype "passive"))
      (node (ref "C27") (pin "1") (pinfunction "1_1") (pintype "passive"))
      (node (ref "C28") (pin "2") (pinfunction "2_2") (pintype "passive"))
      (node (ref "C29") (pin "2") (pinfunction "2_2") (pintype "passive"))
      (node (ref "C3") (pin "2") (pinfunction "2_2") (pintype "passive"))
      (node (ref "C30") (pin "2") (pinfunction "2_2") (pintype "passive"))
      (node (ref "C31") (pin "1") (pinfunction "1_1") (pintype "passive"))
      (node (ref "C33") (pin "1") (pinfunction "1_1") (pintype "passive"))
      (node (ref "C35") (pin "2") (pinfunction "2_2") (pintype "passive"))
      (node (ref "C36") (pin "2") (pinfunction "2_2") (pintype "passive"))
      (node (ref "C37") (pin "2") (pinfunction "-_2") (pintype "passive"))
      (node (ref "C38") (pin "2") (pinfunction "-_2") (pintype "passive"))
      (node (ref "C39") (pin "1") (pinfunction "1_1") (pintype "passive"))
      (node (ref "C4") (pin "1") (pinfunction "1_1") (pintype "passive"))
      (node (ref "C40") (pin "1") (pinfunction "1_1") (pintype "passive"))
      (node (ref "C41") (pin "1") (pinfunction "1_1") (pintype "passive"))
      (node (ref "C42") (pin "1") (pinfunction "1_1") (pintype "passive"))
      (node (ref "C43") (pin "1") (pinfunction "1_1") (pintype "passive"))
      (node (ref "C44") (pin "1") (pinfunction "1_1") (pintype "passive"))
      (node (ref "C5") (pin "1") (pinfunction "1_1") (pintype "passive"))
      (node (ref "C6") (pin "2") (pinfunction "2_2") (pintype "passive"))
      (node (ref "C7") (pin "1") (pinfunction "1_1") (pintype "passive"))
      (node (ref "C8") (pin "2") (pinfunction "2_2") (pintype "passive"))
      (node (ref "C9") (pin "2") (pinfunction "2_2") (pintype "passive"))
      (node (ref "IC1") (pin "5") (pinfunction "GND_5") (pintype "passive"))
      (node (ref "P1") (pin "2") (pinfunction "2_2") (pintype "passive"))
      (node (ref "P485") (pin "2") (pinfunction "2_2") (pintype "passive"))
      (node (ref "PF1") (pin "2") (pinfunction "2_2") (pintype "passive"))
      (node (ref "PL1") (pin "2") (pinfunction "2_2") (pintype "passive"))
      (node (ref "PL2") (pin "2") (pinfunction "2_2") (pintype "passive"))
      (node (ref "PT1") (pin "2") (pinfunction "2_2") (pintype "passive"))
      (node (ref "R1") (pin "1") (pinfunction "1_1") (pintype "passive"))
      (node (ref "R11") (pin "2") (pinfunction "2_2") (pintype "passive"))
      (node (ref "R14") (pin "2") (pinfunction "2_2") (pintype "passive"))
      (node (ref "R15") (pin "2") (pinfunction "2_2") (pintype "passive"))
      (node (ref "R17") (pin "1") (pinfunction "1_1") (pintype "passive"))
      (node (ref "R18") (pin "1") (pinfunction "1_1") (pintype "passive"))
      (node (ref "R19") (pin "2") (pinfunction "2_2") (pintype "passive"))
      (node (ref "R2") (pin "2") (pinfunction "2_2") (pintype "passive"))
      (node (ref "R20") (pin "2") (pinfunction "2_2") (pintype "passive"))
      (node (ref "R22") (pin "2") (pinfunction "2_2") (pintype "passive"))
      (node (ref "R24") (pin "2") (pinfunction "2_2") (pintype "passive"))
      (node (ref "R25") (pin "2") (pinfunction "2_2") (pintype "passive"))
      (node (ref "R26") (pin "2") (pinfunction "2_2") (pintype "passive"))
      (node (ref "R27") (pin "2") (pinfunction "2_2") (pintype "passive"))
      (node (ref "R28") (pin "2") (pinfunction "2_2") (pintype "passive"))
      (node (ref "R29") (pin "2") (pinfunction "2_2") (pintype "passive"))
      (node (ref "R30") (pin "2") (pinfunction "2_2") (pintype "passive"))
      (node (ref "R31") (pin "2") (pinfunction "2_2") (pintype "passive"))
      (node (ref "R40") (pin "2") (pinfunction "2_2") (pintype "passive"))
      (node (ref "R41") (pin "2") (pinfunction "2_2") (pintype "passive"))
      (node (ref "R42") (pin "2") (pinfunction "2_2") (pintype "passive"))
      (node (ref "R43") (pin "2") (pinfunction "2_2") (pintype "passive"))
      (node (ref "R44") (pin "2") (pinfunction "2_2") (pintype "passive"))
      (node (ref "R45") (pin "2") (pinfunction "2_2") (pintype "passive"))
      (node (ref "R46") (pin "2") (pinfunction "2_2") (pintype "passive"))
      (node (ref "R47") (pin "2") (pinfunction "2_2") (pintype "passive"))
      (node (ref "R5") (pin "1") (pinfunction "1_1") (pintype "passive"))
      (node (ref "R7") (pin "1") (pinfunction "1_1") (pintype "passive"))
      (node (ref "R8") (pin "2") (pinfunction "2_2") (pintype "passive"))
      (node (ref "U1") (pin "4") (pinfunction "SRP_4") (pintype "input"))
      (node (ref "U1") (pin "5") (pinfunction "GND_5") (pintype "power_in"))
      (node (ref "U10") (pin "4") (pinfunction "SRP_4") (pintype "input"))
      (node (ref "U10") (pin "5") (pinfunction "GND_5") (pintype "power_in"))
      (node (ref "U11") (pin "14") (pinfunction "GND_14") (pintype "power_in"))
      (node (ref "U11") (pin "24") (pinfunction "MODE0_24") (pintype "input"))
      (node (ref "U11") (pin "25") (pinfunction "MODE1_25") (pintype "input"))
      (node (ref "U11") (pin "26") (pinfunction "MODE2_26") (pintype "input"))
      (node (ref "U11") (pin "28") (pinfunction "GND_28") (pintype "power_in"))
      (node (ref "U11") (pin "29") (pinfunction "GND_29") (pintype "power_in"))
      (node (ref "U12") (pin "1") (pinfunction "Ground_1") (pintype "power_in"))
      (node (ref "U2") (pin "4") (pinfunction "SRP_4") (pintype "input"))
      (node (ref "U2") (pin "5") (pinfunction "GND_5") (pintype "power_in"))
      (node (ref "U3") (pin "4") (pinfunction "SRP_4") (pintype "input"))
      (node (ref "U3") (pin "5") (pinfunction "GND_5") (pintype "power_in"))
      (node (ref "U4") (pin "4") (pinfunction "SRP_4") (pintype "input"))
      (node (ref "U4") (pin "5") (pinfunction "GND_5") (pintype "power_in"))
      (node (ref "U5") (pin "14") (pinfunction "GND_14") (pintype "power_in"))
      (node (ref "U5") (pin "24") (pinfunction "MODE0_24") (pintype "input"))
      (node (ref "U5") (pin "25") (pinfunction "MODE1_25") (pintype "input"))
      (node (ref "U5") (pin "26") (pinfunction "MODE2_26") (pintype "input"))
      (node (ref "U5") (pin "28") (pinfunction "GND_28") (pintype "power_in"))
      (node (ref "U5") (pin "29") (pinfunction "GND_29") (pintype "power_in"))
      (node (ref "U6") (pin "4") (pinfunction "SRP_4") (pintype "input"))
      (node (ref "U6") (pin "5") (pinfunction "GND_5") (pintype "power_in"))
      (node (ref "U7") (pin "4") (pinfunction "SRP_4") (pintype "input"))
      (node (ref "U7") (pin "5") (pinfunction "GND_5") (pintype "power_in"))
      (node (ref "U8") (pin "23") (pinfunction "VSS_23") (pintype "power_in"))
      (node (ref "U8") (pin "47") (pinfunction "VSS_47") (pintype "power_in"))
      (node (ref "U8") (pin "8") (pinfunction "VSSA_8") (pintype "power_in"))
      (node (ref "U9") (pin "4") (pinfunction "SRP_4") (pintype "input"))
      (node (ref "U9") (pin "5") (pinfunction "GND_5") (pintype "power_in"))
      (node (ref "VM") (pin "2") (pinfunction "2_2") (pintype "passive"))
      (node (ref "VR1") (pin "1") (pinfunction "CCW_1") (pintype "passive"))
      (node (ref "VR2") (pin "1") (pinfunction "CCW_1") (pintype "passive"))
      (node (ref "Y1") (pin "2") (pinfunction "GND_1_2") (pintype "passive"))
      (node (ref "Y1") (pin "4") (pinfunction "GND_2_4") (pintype "passive"))
    )
    (net (code "40") (name "Net-(IC1-A)") (class "Default")
      (node (ref "IC1") (pin "6") (pinfunction "A_6") (pintype "passive"))
      (node (ref "P485") (pin "3") (pinfunction "3_3") (pintype "passive"))
      (node (ref "R3") (pin "2") (pinfunction "2_2") (pintype "passive"))
      (node (ref "R6") (pin "1") (pinfunction "1_1") (pintype "passive"))
    )
    (net (code "41") (name "Net-(IC1-B)") (class "Default")
      (node (ref "IC1") (pin "7") (pinfunction "B_7") (pintype "passive"))
      (node (ref "P485") (pin "1") (pinfunction "1_1") (pintype "passive"))
      (node (ref "R1") (pin "2") (pinfunction "2_2") (pintype "passive"))
      (node (ref "R3") (pin "1") (pinfunction "1_1") (pintype "passive"))
    )
    (net (code "42") (name "Net-(U1-DRAIN)") (class "Default")
      (node (ref "U1") (pin "3") (pinfunction "DRAIN_3") (pintype "power_in"))
      (node (ref "VSOL1") (pin "2") (pinfunction "2_2") (pintype "passive"))
    )
    (net (code "43") (name "Net-(U2-DRAIN)") (class "Default")
      (node (ref "U2") (pin "3") (pinfunction "DRAIN_3") (pintype "power_in"))
      (node (ref "VSOL2") (pin "2") (pinfunction "2_2") (pintype "passive"))
    )
    (net (code "44") (name "Net-(U3-DRAIN)") (class "Default")
      (node (ref "U3") (pin "3") (pinfunction "DRAIN_3") (pintype "power_in"))
      (node (ref "VSOL3") (pin "2") (pinfunction "2_2") (pintype "passive"))
    )
    (net (code "45") (name "Net-(U4-DRAIN)") (class "Default")
      (node (ref "U4") (pin "3") (pinfunction "DRAIN_3") (pintype "power_in"))
      (node (ref "VSOL4") (pin "2") (pinfunction "2_2") (pintype "passive"))
    )
    (net (code "46") (name "Net-(U5-AOUT1)") (class "Default")
      (node (ref "PM1") (pin "1") (pinfunction "1_1") (pintype "passive"))
      (node (ref "U5") (pin "5") (pinfunction "AOUT1_5") (pintype "tri_state"))
    )
    (net (code "47") (name "Net-(U5-AOUT2)") (class "Default")
      (node (ref "PM1") (pin "2") (pinfunction "2_2") (pintype "passive"))
      (node (ref "U5") (pin "7") (pinfunction "AOUT2_7") (pintype "tri_state"))
    )
    (net (code "48") (name "Net-(U5-AVREF)") (class "Default")
      (node (ref "U5") (pin "12") (pinfunction "AVREF_12") (pintype "input"))
      (node (ref "U5") (pin "13") (pinfunction "BVREF_13") (pintype "input"))
      (node (ref "VR1") (pin "2") (pinfunction "WIPER_2") (pintype "output"))
    )
    (net (code "49") (name "Net-(U5-BOUT1)") (class "Default")
      (node (ref "PM1") (pin "4") (pinfunction "4_4") (pintype "passive"))
      (node (ref "U5") (pin "10") (pinfunction "BOUT1_10") (pintype "tri_state"))
    )
    (net (code "50") (name "Net-(U5-BOUT2)") (class "Default")
      (node (ref "PM1") (pin "3") (pinfunction "3_3") (pintype "passive"))
      (node (ref "U5") (pin "8") (pinfunction "BOUT2_8") (pintype "tri_state"))
    )
    (net (code "51") (name "Net-(U5-CP1)") (class "Default")
      (node (ref "C11") (pin "2") (pinfunction "2_2") (pintype "passive"))
      (node (ref "U5") (pin "1") (pinfunction "CP1_1") (pintype "passive"))
    )
    (net (code "52") (name "Net-(U5-CP2)") (class "Default")
      (node (ref "C11") (pin "1") (pinfunction "1_1") (pintype "passive"))
      (node (ref "U5") (pin "2") (pinfunction "CP2_2") (pintype "passive"))
    )
    (net (code "53") (name "Net-(U5-ISENA)") (class "Default")
      (node (ref "R8") (pin "1") (pinfunction "1_1") (pintype "passive"))
      (node (ref "U5") (pin "6") (pinfunction "ISENA_6") (pintype "passive"))
    )
    (net (code "54") (name "Net-(U5-ISENB)") (class "Default")
      (node (ref "R11") (pin "1") (pinfunction "1_1") (pintype "passive"))
      (node (ref "U5") (pin "9") (pinfunction "ISENB_9") (pintype "passive"))
    )
    (net (code "55") (name "Net-(U5-V3P3OUT)") (class "Default")
      (node (ref "C13") (pin "2") (pinfunction "2_2") (pintype "passive"))
      (node (ref "U5") (pin "15") (pinfunction "V3P3OUT_15") (pintype "power_in"))
      (node (ref "VR1") (pin "3") (pinfunction "CW_3") (pintype "input"))
    )
    (net (code "56") (name "Net-(U5-VCP)") (class "Default")
      (node (ref "C14") (pin "2") (pinfunction "2_2") (pintype "passive"))
      (node (ref "R12") (pin "2") (pinfunction "2_2") (pintype "passive"))
      (node (ref "U5") (pin "3") (pinfunction "VCP_3") (pintype "passive"))
    )
    (net (code "57") (name "Net-(U6-DRAIN)") (class "Default")
      (node (ref "U6") (pin "3") (pinfunction "DRAIN_3") (pintype "power_in"))
      (node (ref "VSOL5") (pin "2") (pinfunction "2_2") (pintype "passive"))
    )
    (net (code "58") (name "Net-(U7-DRAIN)") (class "Default")
      (node (ref "U7") (pin "3") (pinfunction "DRAIN_3") (pintype "power_in"))
      (node (ref "VSOL6") (pin "2") (pinfunction "2_2") (pintype "passive"))
    )
    (net (code "59") (name "Net-(U8A-BOOT0)") (class "Default")
      (node (ref "R20") (pin "1") (pinfunction "1_1") (pintype "passive"))
      (node (ref "U8") (pin "44") (pinfunction "BOOT0_44") (pintype "passive"))
    )
    (net (code "60") (name "Net-(U8A-PA13(SWDAT))") (class "Default")
      (node (ref "P1") (pin "3") (pinfunction "3_3") (pintype "passive"))
      (node (ref "U8") (pin "34") (pinfunction "PA13(SWDAT)_34") (pintype "bidirectional"))
    )
    (net (code "61") (name "Net-(U8A-PA14(SWCLK))") (class "Default")
      (node (ref "P1") (pin "1") (pinfunction "1_1") (pintype "passive"))
      (node (ref "U8") (pin "37") (pinfunction "PA14(SWCLK)_37") (pintype "bidirectional"))
    )
    (net (code "62") (name "Net-(U8A-PF0-OSC_IN(PF0))") (class "Default")
      (node (ref "C31") (pin "2") (pinfunction "2_2") (pintype "passive"))
      (node (ref "U8") (pin "5") (pinfunction "PF0-OSC_IN(PF0)_5") (pintype "bidirectional"))
      (node (ref "Y1") (pin "3") (pinfunction "CRYSTAL_2_3") (pintype "passive"))
    )
    (net (code "63") (name "Net-(U8A-PF1-OSC_OUT(PF1))") (class "Default")
      (node (ref "C30") (pin "1") (pinfunction "1_1") (pintype "passive"))
      (node (ref "U8") (pin "6") (pinfunction "PF1-OSC_OUT(PF1)_6") (pintype "bidirectional"))
      (node (ref "Y1") (pin "1") (pinfunction "CRYSTAL_1_1") (pintype "passive"))
    )
    (net (code "64") (name "Net-(U9-DRAIN)") (class "Default")
      (node (ref "U9") (pin "3") (pinfunction "DRAIN_3") (pintype "power_in"))
      (node (ref "VSOL7") (pin "2") (pinfunction "2_2") (pintype "passive"))
    )
    (net (code "65") (name "Net-(U10-DRAIN)") (class "Default")
      (node (ref "U10") (pin "3") (pinfunction "DRAIN_3") (pintype "power_in"))
      (node (ref "VSOL8") (pin "2") (pinfunction "2_2") (pintype "passive"))
    )
    (net (code "66") (name "Net-(U11-AOUT1)") (class "Default")
      (node (ref "PM2") (pin "1") (pinfunction "1_1") (pintype "passive"))
      (node (ref "U11") (pin "5") (pinfunction "AOUT1_5") (pintype "tri_state"))
    )
    (net (code "67") (name "Net-(U11-AOUT2)") (class "Default")
      (node (ref "PM2") (pin "2") (pinfunction "2_2") (pintype "passive"))
      (node (ref "U11") (pin "7") (pinfunction "AOUT2_7") (pintype "tri_state"))
    )
    (net (code "68") (name "Net-(U11-AVREF)") (class "Default")
      (node (ref "U11") (pin "12") (pinfunction "AVREF_12") (pintype "input"))
      (node (ref "U11") (pin "13") (pinfunction "BVREF_13") (pintype "input"))
      (node (ref "VR2") (pin "2") (pinfunction "WIPER_2") (pintype "output"))
    )
    (net (code "69") (name "Net-(U11-BOUT1)") (class "Default")
      (node (ref "PM2") (pin "4") (pinfunction "4_4") (pintype "passive"))
      (node (ref "U11") (pin "10") (pinfunction "BOUT1_10") (pintype "tri_state"))
    )
    (net (code "70") (name "Net-(U11-BOUT2)") (class "Default")
      (node (ref "PM2") (pin "3") (pinfunction "3_3") (pintype "passive"))
      (node (ref "U11") (pin "8") (pinfunction "BOUT2_8") (pintype "tri_state"))
    )
    (net (code "71") (name "Net-(U11-CP1)") (class "Default")
      (node (ref "C32") (pin "2") (pinfunction "2_2") (pintype "passive"))
      (node (ref "U11") (pin "1") (pinfunction "CP1_1") (pintype "passive"))
    )
    (net (code "72") (name "Net-(U11-CP2)") (class "Default")
      (node (ref "C32") (pin "1") (pinfunction "1_1") (pintype "passive"))
      (node (ref "U11") (pin "2") (pinfunction "CP2_2") (pintype "passive"))
    )
    (net (code "73") (name "Net-(U11-ISENA)") (class "Default")
      (node (ref "R19") (pin "1") (pinfunction "1_1") (pintype "passive"))
      (node (ref "U11") (pin "6") (pinfunction "ISENA_6") (pintype "passive"))
    )
    (net (code "74") (name "Net-(U11-ISENB)") (class "Default")
      (node (ref "R22") (pin "1") (pinfunction "1_1") (pintype "passive"))
      (node (ref "U11") (pin "9") (pinfunction "ISENB_9") (pintype "passive"))
    )
    (net (code "75") (name "Net-(U11-V3P3OUT)") (class "Default")
      (node (ref "C33") (pin "2") (pinfunction "2_2") (pintype "passive"))
      (node (ref "U11") (pin "15") (pinfunction "V3P3OUT_15") (pintype "power_in"))
      (node (ref "VR2") (pin "3") (pinfunction "CW_3") (pintype "input"))
    )
    (net (code "76") (name "Net-(U11-VCP)") (class "Default")
      (node (ref "C34") (pin "2") (pinfunction "2_2") (pintype "passive"))
      (node (ref "R23") (pin "2") (pinfunction "2_2") (pintype "passive"))
      (node (ref "U11") (pin "3") (pinfunction "VCP_3") (pintype "passive"))
    )
    (net (code "77") (name "VMOT") (class "Default")
      (node (ref "C14") (pin "1") (pinfunction "1_1") (pintype "passive"))
      (node (ref "C16") (pin "2") (pinfunction "2_2") (pintype "passive"))
      (node (ref "C17") (pin "2") (pinfunction "2_2") (pintype "passive"))
      (node (ref "C18") (pin "1") (pinfunction "1_1") (pintype "passive"))
      (node (ref "C19") (pin "1") (pinfunction "1_1") (pintype "passive"))
      (node (ref "C34") (pin "1") (pinfunction "1_1") (pintype "passive"))
      (node (ref "C35") (pin "1") (pinfunction "1_1") (pintype "passive"))
      (node (ref "C36") (pin "1") (pinfunction "1_1") (pintype "passive"))
      (node (ref "C39") (pin "2") (pinfunction "2_2") (pintype "passive"))
      (node (ref "C40") (pin "2") (pinfunction "2_2") (pintype "passive"))
      (node (ref "R12") (pin "1") (pinfunction "1_1") (pintype "passive"))
      (node (ref "R23") (pin "1") (pinfunction "1_1") (pintype "passive"))
      (node (ref "U11") (pin "11") (pinfunction "VMB_11") (pintype "power_in"))
      (node (ref "U11") (pin "4") (pinfunction "VMA_4") (pintype "power_in"))
      (node (ref "U5") (pin "11") (pinfunction "VMB_11") (pintype "power_in"))
      (node (ref "U5") (pin "4") (pinfunction "VMA_4") (pintype "power_in"))
      (node (ref "VM") (pin "1") (pinfunction "1_1") (pintype "passive"))
    )
    (net (code "78") (name "unconnected-(U5-DECAY-Pad19)") (class "Default")
      (node (ref "U5") (pin "19") (pinfunction "DECAY_19") (pintype "input+no_connect"))
    )
    (net (code "79") (name "unconnected-(U5-NC-Pad23)") (class "Default")
      (node (ref "U5") (pin "23") (pinfunction "NC_23") (pintype "passive+no_connect"))
    )
    (net (code "80") (name "unconnected-(U5-NHOME-Pad27)") (class "Default")
      (node (ref "U5") (pin "27") (pinfunction "NHOME_27") (pintype "open_collector+no_connect"))
    )
    (net (code "81") (name "unconnected-(U8A-PC15-OSC32_OUT(PC15)-Pad4)") (class "Default")
      (node (ref "U8") (pin "4") (pinfunction "PC15-OSC32_OUT(PC15)_4") (pintype "bidirectional"))
    )
    (net (code "82") (name "unconnected-(U11-DECAY-Pad19)") (class "Default")
      (node (ref "U11") (pin "19") (pinfunction "DECAY_19") (pintype "input+no_connect"))
    )
    (net (code "83") (name "unconnected-(U11-NC-Pad23)") (class "Default")
      (node (ref "U11") (pin "23") (pinfunction "NC_23") (pintype "passive+no_connect"))
    )
    (net (code "84") (name "unconnected-(U11-NHOME-Pad27)") (class "Default")
      (node (ref "U11") (pin "27") (pinfunction "NHOME_27") (pintype "open_collector+no_connect"))
    )
  )
)
